# Lipmouse_Daughterboard.net
KiCad netlist of a schematic drawn in EAGLE
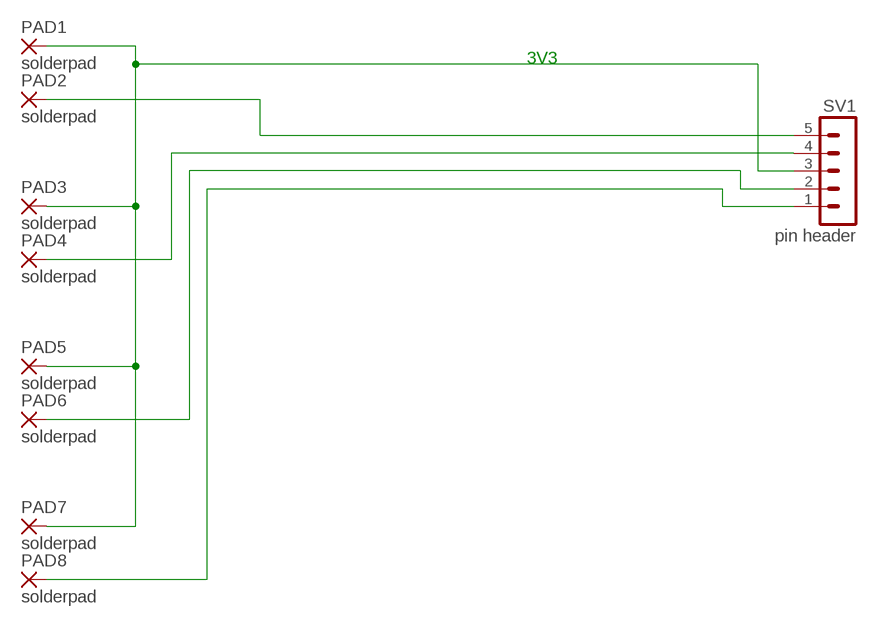
[diagram p0: schematic, sheet 1]

(export (version "E")
  (design (tool "Eeschema 10.0.6"))
  (components
    (comp (ref "PAD1")
      (value "solderpad")
      (footprint "eagle-import:SMD2,54-5,08")
      (libsource (lib "eagle-import") (part "SMD5"))
    )
    (comp (ref "PAD2")
      (value "solderpad")
      (footprint "eagle-import:SMD2,54-5,08")
      (libsource (lib "eagle-import") (part "SMD5"))
    )
    (comp (ref "PAD3")
      (value "solderpad")
      (footprint "eagle-import:SMD2,54-5,08")
      (libsource (lib "eagle-import") (part "SMD5"))
    )
    (comp (ref "PAD4")
      (value "solderpad")
      (footprint "eagle-import:SMD2,54-5,08")
      (libsource (lib "eagle-import") (part "SMD5"))
    )
    (comp (ref "PAD5")
      (value "solderpad")
      (footprint "eagle-import:SMD2,54-5,08")
      (libsource (lib "eagle-import") (part "SMD5"))
    )
    (comp (ref "PAD6")
      (value "solderpad")
      (footprint "eagle-import:SMD2,54-5,08")
      (libsource (lib "eagle-import") (part "SMD5"))
    )
    (comp (ref "PAD7")
      (value "solderpad")
      (footprint "eagle-import:SMD2,54-5,08")
      (libsource (lib "eagle-import") (part "SMD5"))
    )
    (comp (ref "PAD8")
      (value "solderpad")
      (footprint "eagle-import:SMD2,54-5,08")
      (libsource (lib "eagle-import") (part "SMD5"))
    )
    (comp (ref "SV1")
      (value "pin header")
      (footprint "eagle-import:MA05-1")
      (libsource (lib "eagle-import") (part "MA05-1"))
    )
  )
  (nets
    (net (code "1") (name "Net-(PAD1-P)") (class "Default")
      (node (ref "PAD1") (pin "1") (pinfunction "P_1") (pintype "passive"))
      (node (ref "PAD3") (pin "1") (pinfunction "P_1") (pintype "passive"))
      (node (ref "PAD5") (pin "1") (pinfunction "P_1") (pintype "passive"))
      (node (ref "PAD7") (pin "1") (pinfunction "P_1") (pintype "passive"))
      (node (ref "SV1") (pin "3") (pinfunction "3_3") (pintype "passive"))
    )
    (net (code "2") (name "Net-(PAD2-P)") (class "Default")
      (node (ref "PAD2") (pin "1") (pinfunction "P_1") (pintype "passive"))
      (node (ref "SV1") (pin "5") (pinfunction "5_5") (pintype "passive"))
    )
    (net (code "3") (name "Net-(PAD4-P)") (class "Default")
      (node (ref "PAD4") (pin "1") (pinfunction "P_1") (pintype "passive"))
      (node (ref "SV1") (pin "4") (pinfunction "4_4") (pintype "passive"))
    )
    (net (code "4") (name "Net-(PAD6-P)") (class "Default")
      (node (ref "PAD6") (pin "1") (pinfunction "P_1") (pintype "passive"))
      (node (ref "SV1") (pin "2") (pinfunction "2_2") (pintype "passive"))
    )
    (net (code "5") (name "Net-(PAD8-P)") (class "Default")
      (node (ref "PAD8") (pin "1") (pinfunction "P_1") (pintype "passive"))
      (node (ref "SV1") (pin "1") (pinfunction "1_1") (pintype "passive"))
    )
  )
)
